# PowerTowerConnectors.net
KiCad netlist of a schematic drawn in Altium Designer
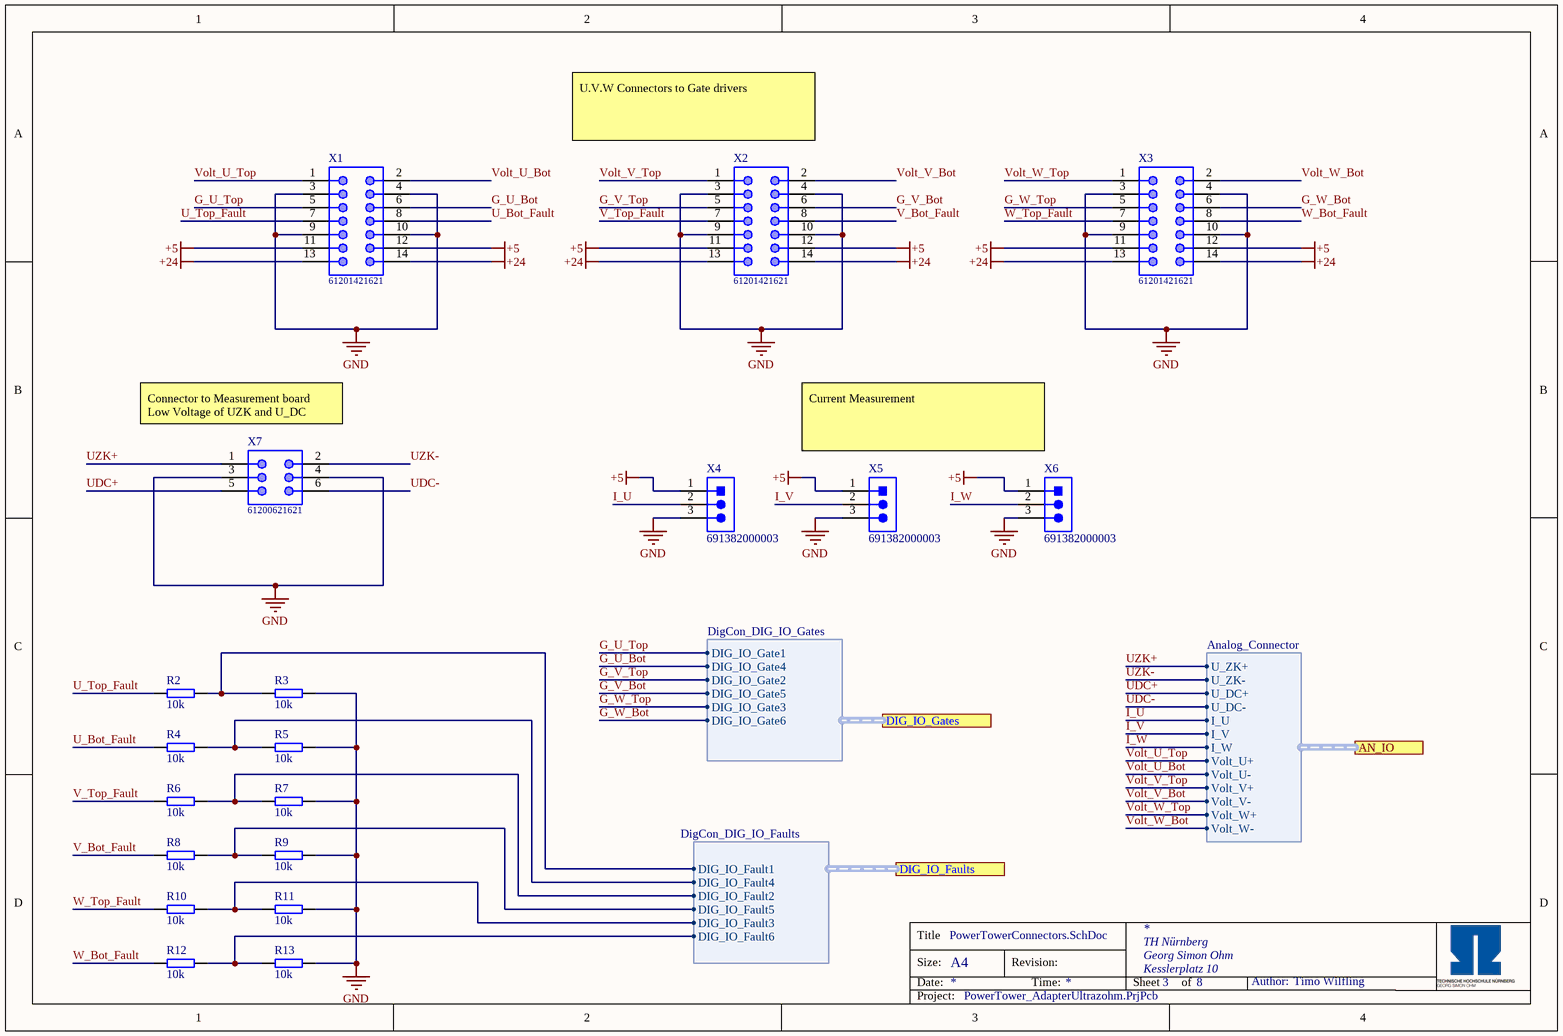
[diagram p0: PowerTowerConnectors.SchDoc]

(export (version "E")
  (design (tool "Eeschema 10.0.6"))
  (components
    (comp (ref "R2")
      (value "10k")
      (footprint "RES 0603_1608")
      (description "SMD resistor E24 series")
      (fields
        (field (name "MANUFACTURER PART NUMBER") "RK73B1JTTD103J")
        (field (name "MANUFACTURER") "KOA Speer")
        (field (name "CREATED FROM") "MGremer")
      )
      (libsource (lib "user") (part "Resistor"))
    )
    (comp (ref "R3")
      (value "10k")
      (footprint "RES 0603_1608")
      (description "SMD resistor E24 series")
      (fields
        (field (name "MANUFACTURER PART NUMBER") "RK73B1JTTD103J")
        (field (name "MANUFACTURER") "KOA Speer")
        (field (name "CREATED FROM") "MGremer")
      )
      (libsource (lib "user") (part "Resistor"))
    )
    (comp (ref "R4")
      (value "10k")
      (footprint "RES 0603_1608")
      (description "SMD resistor E24 series")
      (fields
        (field (name "MANUFACTURER PART NUMBER") "RK73B1JTTD103J")
        (field (name "MANUFACTURER") "KOA Speer")
        (field (name "CREATED FROM") "MGremer")
      )
      (libsource (lib "user") (part "Resistor"))
    )
    (comp (ref "R5")
      (value "10k")
      (footprint "RES 0603_1608")
      (description "SMD resistor E24 series")
      (fields
        (field (name "MANUFACTURER PART NUMBER") "RK73B1JTTD103J")
        (field (name "MANUFACTURER") "KOA Speer")
        (field (name "CREATED FROM") "MGremer")
      )
      (libsource (lib "user") (part "Resistor"))
    )
    (comp (ref "R6")
      (value "10k")
      (footprint "RES 0603_1608")
      (description "SMD resistor E24 series")
      (fields
        (field (name "MANUFACTURER PART NUMBER") "RK73B1JTTD103J")
        (field (name "MANUFACTURER") "KOA Speer")
        (field (name "CREATED FROM") "MGremer")
      )
      (libsource (lib "user") (part "Resistor"))
    )
    (comp (ref "R7")
      (value "10k")
      (footprint "RES 0603_1608")
      (description "SMD resistor E24 series")
      (fields
        (field (name "MANUFACTURER PART NUMBER") "RK73B1JTTD103J")
        (field (name "MANUFACTURER") "KOA Speer")
        (field (name "CREATED FROM") "MGremer")
      )
      (libsource (lib "user") (part "Resistor"))
    )
    (comp (ref "R8")
      (value "10k")
      (footprint "RES 0603_1608")
      (description "SMD resistor E24 series")
      (fields
        (field (name "MANUFACTURER PART NUMBER") "RK73B1JTTD103J")
        (field (name "MANUFACTURER") "KOA Speer")
        (field (name "CREATED FROM") "MGremer")
      )
      (libsource (lib "user") (part "Resistor"))
    )
    (comp (ref "R9")
      (value "10k")
      (footprint "RES 0603_1608")
      (description "SMD resistor E24 series")
      (fields
        (field (name "MANUFACTURER PART NUMBER") "RK73B1JTTD103J")
        (field (name "MANUFACTURER") "KOA Speer")
        (field (name "CREATED FROM") "MGremer")
      )
      (libsource (lib "user") (part "Resistor"))
    )
    (comp (ref "R10")
      (value "10k")
      (footprint "RES 0603_1608")
      (description "SMD resistor E24 series")
      (fields
        (field (name "MANUFACTURER PART NUMBER") "RK73B1JTTD103J")
        (field (name "MANUFACTURER") "KOA Speer")
        (field (name "CREATED FROM") "MGremer")
      )
      (libsource (lib "user") (part "Resistor"))
    )
    (comp (ref "R11")
      (value "10k")
      (footprint "RES 0603_1608")
      (description "SMD resistor E24 series")
      (fields
        (field (name "MANUFACTURER PART NUMBER") "RK73B1JTTD103J")
        (field (name "MANUFACTURER") "KOA Speer")
        (field (name "CREATED FROM") "MGremer")
      )
      (libsource (lib "user") (part "Resistor"))
    )
    (comp (ref "R12")
      (value "10k")
      (footprint "RES 0603_1608")
      (description "SMD resistor E24 series")
      (fields
        (field (name "MANUFACTURER PART NUMBER") "RK73B1JTTD103J")
        (field (name "MANUFACTURER") "KOA Speer")
        (field (name "CREATED FROM") "MGremer")
      )
      (libsource (lib "user") (part "Resistor"))
    )
    (comp (ref "R13")
      (value "10k")
      (footprint "RES 0603_1608")
      (description "SMD resistor E24 series")
      (fields
        (field (name "MANUFACTURER PART NUMBER") "RK73B1JTTD103J")
        (field (name "MANUFACTURER") "KOA Speer")
        (field (name "CREATED FROM") "MGremer")
      )
      (libsource (lib "user") (part "Resistor"))
    )
    (comp (ref "X1")
      (value "61201421621")
      (footprint "61201421621")
      (description "2.54mm Double Row 14-pol Vertical Male Pin Box Header")
      (fields (field (name "MANUFACTURER") "Wurth") (field (name "CREATED FROM") "TWilfling"))
      (libsource (lib "user") (part "61201421621"))
    )
    (comp (ref "X2")
      (value "61201421621")
      (footprint "61201421621")
      (description "2.54mm Double Row 14-pol Vertical Male Pin Box Header")
      (fields (field (name "MANUFACTURER") "Wurth") (field (name "CREATED FROM") "TWilfling"))
      (libsource (lib "user") (part "61201421621"))
    )
    (comp (ref "X3")
      (value "61201421621")
      (footprint "61201421621")
      (description "2.54mm Double Row 14-pol Vertical Male Pin Box Header")
      (fields (field (name "MANUFACTURER") "Wurth") (field (name "CREATED FROM") "TWilfling"))
      (libsource (lib "user") (part "61201421621"))
    )
    (comp (ref "X4")
      (value "691382000003")
      (footprint "691382000003")
      (description "2.5mm Single Row 3-pol Vertical PCB Header")
      (fields (field (name "MANUFACTURER") "Wurth") (field (name "CREATED FROM") "TWilfling"))
      (libsource (lib "user") (part "691382000003"))
    )
    (comp (ref "X5")
      (value "691382000003")
      (footprint "691382000003")
      (description "2.5mm Single Row 3-pol Vertical PCB Header")
      (fields (field (name "MANUFACTURER") "Wurth") (field (name "CREATED FROM") "TWilfling"))
      (libsource (lib "user") (part "691382000003"))
    )
    (comp (ref "X6")
      (value "691382000003")
      (footprint "691382000003")
      (description "2.5mm Single Row 3-pol Vertical PCB Header")
      (fields (field (name "MANUFACTURER") "Wurth") (field (name "CREATED FROM") "TWilfling"))
      (libsource (lib "user") (part "691382000003"))
    )
    (comp (ref "X7")
      (value "61200621621")
      (footprint "61200621621")
      (description "2.54mm Double Row 6-pol Vertical Male Pin Box Header")
      (fields (field (name "MANUFACTURER") "Wurth") (field (name "CREATED FROM") "TWilfling"))
      (libsource (lib "user") (part "61200621621"))
    )
  )
  (nets
    (net (code "4") (name "+5") (class "Default")
      (node (ref "X1") (pin "11") (pinfunction "11_11") (pintype "passive"))
      (node (ref "X1") (pin "12") (pinfunction "12_12") (pintype "passive"))
      (node (ref "X2") (pin "11") (pinfunction "11_11") (pintype "passive"))
      (node (ref "X2") (pin "12") (pinfunction "12_12") (pintype "passive"))
      (node (ref "X3") (pin "11") (pinfunction "11_11") (pintype "passive"))
      (node (ref "X3") (pin "12") (pinfunction "12_12") (pintype "passive"))
      (node (ref "X4") (pin "1") (pinfunction "1_1") (pintype "passive"))
      (node (ref "X5") (pin "1") (pinfunction "1_1") (pintype "passive"))
      (node (ref "X6") (pin "1") (pinfunction "1_1") (pintype "passive"))
    )
    (net (code "5") (name "+24") (class "Default")
      (node (ref "X1") (pin "13") (pinfunction "13_13") (pintype "passive"))
      (node (ref "X1") (pin "14") (pinfunction "14_14") (pintype "passive"))
      (node (ref "X2") (pin "13") (pinfunction "13_13") (pintype "passive"))
      (node (ref "X2") (pin "14") (pinfunction "14_14") (pintype "passive"))
      (node (ref "X3") (pin "13") (pinfunction "13_13") (pintype "passive"))
      (node (ref "X3") (pin "14") (pinfunction "14_14") (pintype "passive"))
    )
    (net (code "6") (name "/G_U_Bot") (class "Default")
      (node (ref "X1") (pin "6") (pinfunction "6_6") (pintype "passive"))
    )
    (net (code "7") (name "/G_U_Top") (class "Default")
      (node (ref "X1") (pin "5") (pinfunction "5_5") (pintype "passive"))
    )
    (net (code "8") (name "/G_V_Bot") (class "Default")
      (node (ref "X2") (pin "6") (pinfunction "6_6") (pintype "passive"))
    )
    (net (code "9") (name "/G_V_Top") (class "Default")
      (node (ref "X2") (pin "5") (pinfunction "5_5") (pintype "passive"))
    )
    (net (code "10") (name "/G_W_Bot") (class "Default")
      (node (ref "X3") (pin "6") (pinfunction "6_6") (pintype "passive"))
    )
    (net (code "11") (name "/G_W_Top") (class "Default")
      (node (ref "X3") (pin "5") (pinfunction "5_5") (pintype "passive"))
    )
    (net (code "12") (name "/I_U") (class "Default")
      (node (ref "X4") (pin "2") (pinfunction "2_2") (pintype "passive"))
    )
    (net (code "13") (name "/I_V") (class "Default")
      (node (ref "X5") (pin "2") (pinfunction "2_2") (pintype "passive"))
    )
    (net (code "14") (name "/I_W") (class "Default")
      (node (ref "X6") (pin "2") (pinfunction "2_2") (pintype "passive"))
    )
    (net (code "15") (name "/UDC+") (class "Default")
      (node (ref "X7") (pin "5") (pinfunction "5_5") (pintype "passive"))
    )
    (net (code "16") (name "/UDC-") (class "Default")
      (node (ref "X7") (pin "6") (pinfunction "6_6") (pintype "passive"))
    )
    (net (code "17") (name "/UZK+") (class "Default")
      (node (ref "X7") (pin "1") (pinfunction "1_1") (pintype "passive"))
    )
    (net (code "18") (name "/UZK-") (class "Default")
      (node (ref "X7") (pin "2") (pinfunction "2_2") (pintype "passive"))
    )
    (net (code "19") (name "/U_Bot_Fault") (class "Default")
      (node (ref "R4") (pin "1") (pinfunction "1_1") (pintype "passive"))
      (node (ref "X1") (pin "8") (pinfunction "8_8") (pintype "passive"))
    )
    (net (code "20") (name "/U_Top_Fault") (class "Default")
      (node (ref "R2") (pin "1") (pinfunction "1_1") (pintype "passive"))
      (node (ref "X1") (pin "7") (pinfunction "7_7") (pintype "passive"))
    )
    (net (code "21") (name "/V_Bot_Fault") (class "Default")
      (node (ref "R8") (pin "1") (pinfunction "1_1") (pintype "passive"))
      (node (ref "X2") (pin "8") (pinfunction "8_8") (pintype "passive"))
    )
    (net (code "22") (name "/V_Top_Fault") (class "Default")
      (node (ref "R6") (pin "1") (pinfunction "1_1") (pintype "passive"))
      (node (ref "X2") (pin "7") (pinfunction "7_7") (pintype "passive"))
    )
    (net (code "23") (name "/Volt_U_Bot") (class "Default")
      (node (ref "X1") (pin "2") (pinfunction "2_2") (pintype "passive"))
    )
    (net (code "24") (name "/Volt_U_Top") (class "Default")
      (node (ref "X1") (pin "1") (pinfunction "1_1") (pintype "passive"))
    )
    (net (code "25") (name "/Volt_V_Bot") (class "Default")
      (node (ref "X2") (pin "2") (pinfunction "2_2") (pintype "passive"))
    )
    (net (code "26") (name "/Volt_V_Top") (class "Default")
      (node (ref "X2") (pin "1") (pinfunction "1_1") (pintype "passive"))
    )
    (net (code "27") (name "/Volt_W_Bot") (class "Default")
      (node (ref "X3") (pin "2") (pinfunction "2_2") (pintype "passive"))
    )
    (net (code "28") (name "/Volt_W_Top") (class "Default")
      (node (ref "X3") (pin "1") (pinfunction "1_1") (pintype "passive"))
    )
    (net (code "29") (name "/W_Bot_Fault") (class "Default")
      (node (ref "R12") (pin "1") (pinfunction "1_1") (pintype "passive"))
      (node (ref "X3") (pin "8") (pinfunction "8_8") (pintype "passive"))
    )
    (net (code "30") (name "/W_Top_Fault") (class "Default")
      (node (ref "R10") (pin "1") (pinfunction "1_1") (pintype "passive"))
      (node (ref "X3") (pin "7") (pinfunction "7_7") (pintype "passive"))
    )
    (net (code "34") (name "GND") (class "Default")
      (node (ref "R11") (pin "2") (pinfunction "2_2") (pintype "passive"))
      (node (ref "R13") (pin "2") (pinfunction "2_2") (pintype "passive"))
      (node (ref "R3") (pin "2") (pinfunction "2_2") (pintype "passive"))
      (node (ref "R5") (pin "2") (pinfunction "2_2") (pintype "passive"))
      (node (ref "R7") (pin "2") (pinfunction "2_2") (pintype "passive"))
      (node (ref "R9") (pin "2") (pinfunction "2_2") (pintype "passive"))
      (node (ref "X1") (pin "10") (pinfunction "10_10") (pintype "passive"))
      (node (ref "X1") (pin "3") (pinfunction "3_3") (pintype "passive"))
      (node (ref "X1") (pin "4") (pinfunction "4_4") (pintype "passive"))
      (node (ref "X1") (pin "9") (pinfunction "9_9") (pintype "passive"))
      (node (ref "X2") (pin "10") (pinfunction "10_10") (pintype "passive"))
      (node (ref "X2") (pin "3") (pinfunction "3_3") (pintype "passive"))
      (node (ref "X2") (pin "4") (pinfunction "4_4") (pintype "passive"))
      (node (ref "X2") (pin "9") (pinfunction "9_9") (pintype "passive"))
      (node (ref "X3") (pin "10") (pinfunction "10_10") (pintype "passive"))
      (node (ref "X3") (pin "3") (pinfunction "3_3") (pintype "passive"))
      (node (ref "X3") (pin "4") (pinfunction "4_4") (pintype "passive"))
      (node (ref "X3") (pin "9") (pinfunction "9_9") (pintype "passive"))
      (node (ref "X4") (pin "3") (pinfunction "3_3") (pintype "passive"))
      (node (ref "X5") (pin "3") (pinfunction "3_3") (pintype "passive"))
      (node (ref "X6") (pin "3") (pinfunction "3_3") (pintype "passive"))
      (node (ref "X7") (pin "3") (pinfunction "3_3") (pintype "passive"))
      (node (ref "X7") (pin "4") (pinfunction "4_4") (pintype "passive"))
    )
    (net (code "35") (name "Net-(R2-Pad2)") (class "Default")
      (node (ref "R2") (pin "2") (pinfunction "2_2") (pintype "passive"))
      (node (ref "R3") (pin "1") (pinfunction "1_1") (pintype "passive"))
    )
    (net (code "36") (name "Net-(R4-Pad2)") (class "Default")
      (node (ref "R4") (pin "2") (pinfunction "2_2") (pintype "passive"))
      (node (ref "R5") (pin "1") (pinfunction "1_1") (pintype "passive"))
    )
    (net (code "37") (name "Net-(R6-Pad2)") (class "Default")
      (node (ref "R6") (pin "2") (pinfunction "2_2") (pintype "passive"))
      (node (ref "R7") (pin "1") (pinfunction "1_1") (pintype "passive"))
    )
    (net (code "38") (name "Net-(R8-Pad2)") (class "Default")
      (node (ref "R8") (pin "2") (pinfunction "2_2") (pintype "passive"))
      (node (ref "R9") (pin "1") (pinfunction "1_1") (pintype "passive"))
    )
    (net (code "39") (name "Net-(R10-Pad2)") (class "Default")
      (node (ref "R10") (pin "2") (pinfunction "2_2") (pintype "passive"))
      (node (ref "R11") (pin "1") (pinfunction "1_1") (pintype "passive"))
    )
    (net (code "40") (name "Net-(R12-Pad2)") (class "Default")
      (node (ref "R12") (pin "2") (pinfunction "2_2") (pintype "passive"))
      (node (ref "R13") (pin "1") (pinfunction "1_1") (pintype "passive"))
    )
  )
)
